# Sound.net
KiCad netlist of a schematic drawn in Altium Designer
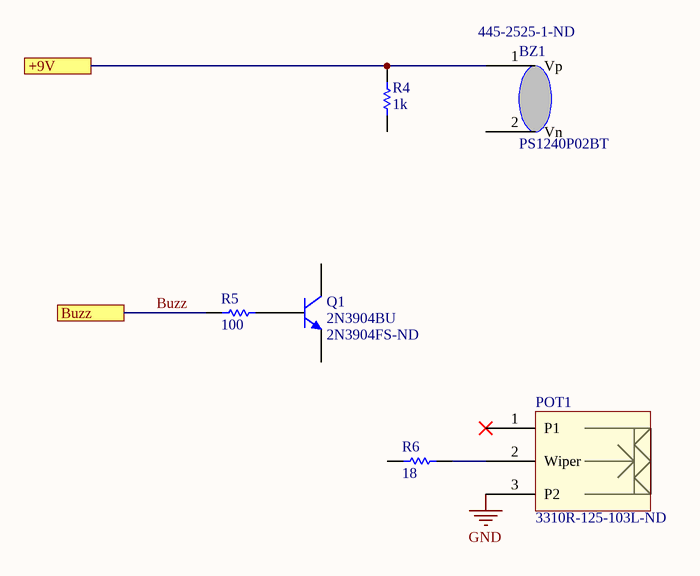
[diagram p0: Sound.SchDoc]

(export (version "E")
  (design (tool "Eeschema 10.0.6"))
  (components
    (comp (ref "BZ1")
      (value "PS1240P02BT")
      (footprint "PS1240P02BT")
      (description "Piezo Buzzer, Through Hole")
      (fields (field (name "SUPPLIER PART NUMBER 1") "445-2525-1-ND"))
      (libsource (lib "ServoInterface") (part "PS12"))
    )
    (comp (ref "POT1")
      (value "3310R-125-103L")
      (footprint "3310R-001")
      (description "POT 10K OHM 1/4W PLASTIC LINEAR")
      (fields (field (name "SUPPLIER PART NUMBER 1") "3310R-125-103L-ND"))
      (libsource (lib "ServoInterface") (part "Potentiometer - 10k"))
    )
    (comp (ref "Q1")
      (value "2N3904BU")
      (footprint "2N3904")
      (description "TRANS NPN 40V 0.2A TO-92")
      (fields
        (field (name "SUPPLIER PART NUMBER 1") "2N3904FS-ND")
        (field (name "PUBLISHER") "Altium Limited")
      )
      (libsource (lib "ServoInterface") (part "2N3904"))
    )
    (comp (ref "R4")
      (value "1k")
      (footprint "Resistor Through Hole")
      (description "CF14JT1K00")
      (libsource (lib "ServoInterface") (part "Resistor_1k"))
    )
    (comp (ref "R5")
      (value "100")
      (footprint "Resistor Through Hole")
      (description "CF14JT100R")
      (libsource (lib "ServoInterface") (part "Resistor_100"))
    )
    (comp (ref "R6")
      (value "18")
      (footprint "Resistor Through Hole")
      (description "CF14JT18R0")
      (libsource (lib "ServoInterface") (part "Resistor_18"))
    )
  )
  (nets
    (net (code "1") (name "/+9V") (class "Default")
      (node (ref "BZ1") (pin "1") (pinfunction "Vp_1") (pintype "passive"))
      (node (ref "R4") (pin "1") (pinfunction "1_1") (pintype "passive"))
    )
    (net (code "2") (name "/Buzz") (class "Default")
      (node (ref "R5") (pin "2") (pinfunction "2_2") (pintype "passive"))
    )
    (net (code "3") (name "GND") (class "Default")
      (node (ref "POT1") (pin "3") (pinfunction "P2_3") (pintype "passive"))
    )
    (net (code "4") (name "Net-(POT1-Wiper)") (class "Default")
      (node (ref "POT1") (pin "2") (pinfunction "Wiper_2") (pintype "passive"))
      (node (ref "R6") (pin "1") (pinfunction "1_1") (pintype "passive"))
    )
    (net (code "5") (name "Net-(Q1-B)") (class "Default")
      (node (ref "Q1") (pin "2") (pinfunction "B_2") (pintype "passive"))
      (node (ref "R5") (pin "1") (pinfunction "1_1") (pintype "passive"))
    )
    (net (code "6") (name "unconnected-(BZ1-Vn-Pad2)") (class "Default")
      (node (ref "BZ1") (pin "2") (pinfunction "Vn_2") (pintype "passive"))
    )
    (net (code "7") (name "unconnected-(POT1-P1-Pad1)") (class "Default")
      (node (ref "POT1") (pin "1") (pinfunction "P1_1") (pintype "passive+no_connect"))
    )
    (net (code "8") (name "unconnected-(Q1-C-Pad3)") (class "Default")
      (node (ref "Q1") (pin "3") (pinfunction "C_3") (pintype "passive"))
    )
    (net (code "9") (name "unconnected-(Q1-E-Pad1)") (class "Default")
      (node (ref "Q1") (pin "1") (pinfunction "E_1") (pintype "passive"))
    )
    (net (code "10") (name "unconnected-(R4-Pad2)") (class "Default")
      (node (ref "R4") (pin "2") (pinfunction "2_2") (pintype "passive"))
    )
    (net (code "11") (name "unconnected-(R6-Pad2)") (class "Default")
      (node (ref "R6") (pin "2") (pinfunction "2_2") (pintype "passive"))
    )
  )
)
